# MBusUART.net
KiCad netlist of a schematic drawn in EAGLE
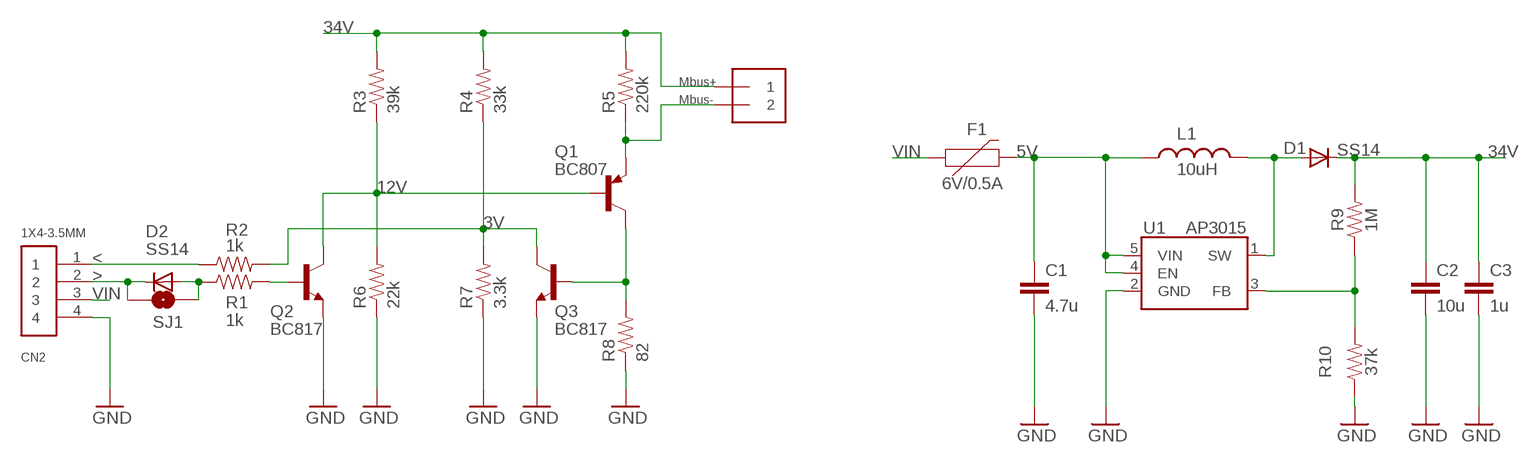
[diagram p0: schematic, sheet 1]

(export (version "E")
  (design (tool "Eeschema 10.0.6"))
  (components
    (comp (ref "C1")
      (value "4.7u")
      (footprint "eagle-import:0805")
      (libsource (lib "eagle-import") (part "1.0UF-0805-25V-(+80/-20%)"))
    )
    (comp (ref "C2")
      (value "10u")
      (footprint "eagle-import:1206")
      (libsource (lib "eagle-import") (part "1.0UF-1206-50V-10%"))
    )
    (comp (ref "C3")
      (value "1u")
      (footprint "eagle-import:1206")
      (libsource (lib "eagle-import") (part "1.0UF-1206-50V-10%"))
    )
    (comp (ref "CN2")
      (value "1X4-3.5MM")
      (footprint "eagle-import:1X04-3.5MM")
      (libsource (lib "eagle-import") (part "1X4-3.5MM"))
    )
    (comp (ref "D1")
      (value "SS14")
      (footprint "eagle-import:SOD-123")
      (libsource (lib "eagle-import") (part "DIODESOD-123"))
    )
    (comp (ref "D2")
      (value "SS14")
      (footprint "eagle-import:SOD-123")
      (libsource (lib "eagle-import") (part "DIODESOD-123"))
    )
    (comp (ref "F1")
      (value "6V/0.5A")
      (footprint "eagle-import:1206")
      (libsource (lib "eagle-import") (part "PPTC_HALF-AMP"))
    )
    (comp (ref "J1")
      (value "1X2-3.5MM")
      (footprint "eagle-import:1X2-3.5MM")
      (libsource (lib "eagle-import") (part "1X2-3.5MM"))
    )
    (comp (ref "L1")
      (value "10uH")
      (footprint "eagle-import:CR54")
      (libsource (lib "eagle-import") (part "INDUCTORCR54"))
    )
    (comp (ref "Q1")
      (value "BC807")
      (footprint "eagle-import:SOT23-BEC")
      (libsource (lib "eagle-import") (part "-PNP-SOT23-BECBC807-16"))
    )
    (comp (ref "Q2")
      (value "BC817")
      (footprint "eagle-import:SOT23-BEC")
      (libsource (lib "eagle-import") (part "BC817SMD-16"))
    )
    (comp (ref "Q3")
      (value "BC817")
      (footprint "eagle-import:SOT23-BEC")
      (libsource (lib "eagle-import") (part "BC817SMD-16"))
    )
    (comp (ref "R1")
      (value "1k")
      (footprint "eagle-import:0805")
      (libsource (lib "eagle-import") (part "RESISTOR0805"))
    )
    (comp (ref "R2")
      (value "1k")
      (footprint "eagle-import:0805")
      (libsource (lib "eagle-import") (part "RESISTOR0805"))
    )
    (comp (ref "R3")
      (value "39k")
      (footprint "eagle-import:0805")
      (libsource (lib "eagle-import") (part "RESISTOR0805"))
    )
    (comp (ref "R4")
      (value "33k")
      (footprint "eagle-import:0805")
      (libsource (lib "eagle-import") (part "RESISTOR0805"))
    )
    (comp (ref "R5")
      (value "220k")
      (footprint "eagle-import:1206")
      (libsource (lib "eagle-import") (part "RESISTOR1206"))
    )
    (comp (ref "R6")
      (value "22k")
      (footprint "eagle-import:0805")
      (libsource (lib "eagle-import") (part "RESISTOR0805"))
    )
    (comp (ref "R7")
      (value "3.3k")
      (footprint "eagle-import:0805")
      (libsource (lib "eagle-import") (part "RESISTOR0805"))
    )
    (comp (ref "R8")
      (value "82")
      (footprint "eagle-import:1206")
      (libsource (lib "eagle-import") (part "RESISTOR1206"))
    )
    (comp (ref "R9")
      (value "1M")
      (footprint "eagle-import:0805")
      (libsource (lib "eagle-import") (part "RESISTOR0805"))
    )
    (comp (ref "R10")
      (value "37k")
      (footprint "eagle-import:0805")
      (libsource (lib "eagle-import") (part "RESISTOR0805"))
    )
    (comp (ref "SJ1")
      (value "SOLDERJUMPERNO")
      (footprint "eagle-import:SJ_2S-NO")
      (libsource (lib "eagle-import") (part "SOLDERJUMPERNO"))
    )
    (comp (ref "U1")
      (value "AP3015")
      (footprint "eagle-import:SOT-23-5")
      (libsource (lib "eagle-import") (part "AP3015"))
    )
  )
  (nets
    (net (code "1") (name "/3V") (class "Default")
      (node (ref "Q3") (pin "C") (pinfunction "C_C") (pintype "passive"))
      (node (ref "R2") (pin "2") (pinfunction "2_2") (pintype "passive"))
      (node (ref "R4") (pin "1") (pinfunction "1_1") (pintype "passive"))
      (node (ref "R7") (pin "2") (pinfunction "2_2") (pintype "passive"))
    )
    (net (code "2") (name "/5V") (class "Default")
      (node (ref "C1") (pin "1") (pinfunction "1_1") (pintype "passive"))
      (node (ref "F1") (pin "2") (pinfunction "2_2") (pintype "bidirectional"))
      (node (ref "L1") (pin "P$1") (pinfunction "1_P$1") (pintype "passive"))
      (node (ref "U1") (pin "4") (pinfunction "EN_4") (pintype "input"))
      (node (ref "U1") (pin "5") (pinfunction "VIN_5") (pintype "power_in"))
    )
    (net (code "3") (name "/12V") (class "Default")
      (node (ref "Q1") (pin "B") (pinfunction "B_B") (pintype "passive"))
      (node (ref "Q2") (pin "C") (pinfunction "C_C") (pintype "passive"))
      (node (ref "R3") (pin "1") (pinfunction "1_1") (pintype "passive"))
      (node (ref "R6") (pin "2") (pinfunction "2_2") (pintype "passive"))
    )
    (net (code "4") (name "/34V") (class "Default")
      (node (ref "C2") (pin "1") (pinfunction "1_1") (pintype "passive"))
      (node (ref "C3") (pin "1") (pinfunction "1_1") (pintype "passive"))
      (node (ref "D1") (pin "C") (pinfunction "C_C") (pintype "passive"))
      (node (ref "J1") (pin "1") (pinfunction "1_1") (pintype "passive"))
      (node (ref "R3") (pin "2") (pinfunction "2_2") (pintype "passive"))
      (node (ref "R4") (pin "2") (pinfunction "2_2") (pintype "passive"))
      (node (ref "R5") (pin "2") (pinfunction "2_2") (pintype "passive"))
      (node (ref "R9") (pin "2") (pinfunction "2_2") (pintype "passive"))
    )
    (net (code "5") (name "/<") (class "Default")
      (node (ref "CN2") (pin "1") (pinfunction "1_1") (pintype "bidirectional"))
      (node (ref "R2") (pin "1") (pinfunction "1_1") (pintype "passive"))
    )
    (net (code "6") (name "/>") (class "Default")
      (node (ref "CN2") (pin "2") (pinfunction "2_2") (pintype "bidirectional"))
      (node (ref "D2") (pin "C") (pinfunction "C_C") (pintype "passive"))
      (node (ref "SJ1") (pin "1") (pinfunction "1_1") (pintype "passive"))
    )
    (net (code "7") (name "/VIN") (class "Default")
      (node (ref "CN2") (pin "3") (pinfunction "3_3") (pintype "bidirectional"))
      (node (ref "F1") (pin "1") (pinfunction "1_1") (pintype "bidirectional"))
    )
    (net (code "8") (name "GND") (class "Default")
      (node (ref "C1") (pin "2") (pinfunction "2_2") (pintype "passive"))
      (node (ref "C2") (pin "2") (pinfunction "2_2") (pintype "passive"))
      (node (ref "C3") (pin "2") (pinfunction "2_2") (pintype "passive"))
      (node (ref "CN2") (pin "4") (pinfunction "4_4") (pintype "bidirectional"))
      (node (ref "Q2") (pin "E") (pinfunction "E_E") (pintype "passive"))
      (node (ref "Q3") (pin "E") (pinfunction "E_E") (pintype "passive"))
      (node (ref "R10") (pin "1") (pinfunction "1_1") (pintype "passive"))
      (node (ref "R6") (pin "1") (pinfunction "1_1") (pintype "passive"))
      (node (ref "R7") (pin "1") (pinfunction "1_1") (pintype "passive"))
      (node (ref "R8") (pin "1") (pinfunction "1_1") (pintype "passive"))
      (node (ref "U1") (pin "2") (pinfunction "GND_2") (pintype "power_in"))
    )
    (net (code "9") (name "Net-(D2-PadA)") (class "Default")
      (node (ref "D2") (pin "A") (pinfunction "A_A") (pintype "passive"))
      (node (ref "R1") (pin "1") (pinfunction "1_1") (pintype "passive"))
      (node (ref "SJ1") (pin "2") (pinfunction "2_2") (pintype "passive"))
    )
    (net (code "10") (name "Net-(J1-Pad2)") (class "Default")
      (node (ref "J1") (pin "2") (pinfunction "2_2") (pintype "passive"))
      (node (ref "Q1") (pin "E") (pinfunction "E_E") (pintype "passive"))
      (node (ref "R5") (pin "1") (pinfunction "1_1") (pintype "passive"))
    )
    (net (code "11") (name "Net-(L1-2)") (class "Default")
      (node (ref "D1") (pin "A") (pinfunction "A_A") (pintype "passive"))
      (node (ref "L1") (pin "P$2") (pinfunction "2_P$2") (pintype "passive"))
      (node (ref "U1") (pin "1") (pinfunction "SW_1") (pintype "output"))
    )
    (net (code "12") (name "Net-(Q1-PadC)") (class "Default")
      (node (ref "Q1") (pin "C") (pinfunction "C_C") (pintype "passive"))
      (node (ref "Q3") (pin "B") (pinfunction "B_B") (pintype "passive"))
      (node (ref "R8") (pin "2") (pinfunction "2_2") (pintype "passive"))
    )
    (net (code "13") (name "Net-(Q2-PadB)") (class "Default")
      (node (ref "Q2") (pin "B") (pinfunction "B_B") (pintype "passive"))
      (node (ref "R1") (pin "2") (pinfunction "2_2") (pintype "passive"))
    )
    (net (code "14") (name "Net-(U1-FB)") (class "Default")
      (node (ref "R10") (pin "2") (pinfunction "2_2") (pintype "passive"))
      (node (ref "R9") (pin "1") (pinfunction "1_1") (pintype "passive"))
      (node (ref "U1") (pin "3") (pinfunction "FB_3") (pintype "input"))
    )
  )
)
